# NIBB.net
KiCad netlist of a schematic drawn in EAGLE
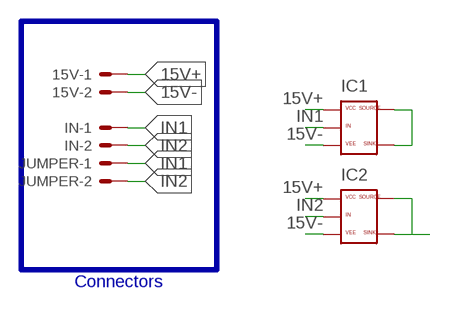
[diagram p0: schematic, sheet 1]

(export (version "E")
  (design (tool "Eeschema 10.0.6"))
  (components
    (comp (ref "15V")
      (value "22-23-2021")
      (footprint "eagle-import:22-23-2021")
      (fields (field (name "MF") "MOLEX"))
      (libsource (lib "eagle-import") (part "22-23-2021"))
    )
    (comp (ref "IC1")
      (value "ZXGD3006E6")
      (footprint "eagle-import:SOT23")
      (libsource (lib "eagle-import") (part "ZXGD3006E6"))
    )
    (comp (ref "IC2")
      (value "ZXGD3006E6")
      (footprint "eagle-import:SOT23")
      (libsource (lib "eagle-import") (part "ZXGD3006E6"))
    )
    (comp (ref "IN")
      (value "22-23-2021")
      (footprint "eagle-import:22-23-2021")
      (fields (field (name "MF") "MOLEX"))
      (libsource (lib "eagle-import") (part "22-23-2021"))
    )
    (comp (ref "JUMPER")
      (value "22-23-2021")
      (footprint "eagle-import:22-23-2021")
      (fields (field (name "MF") "MOLEX"))
      (libsource (lib "eagle-import") (part "22-23-2021"))
    )
  )
  (nets
    (net (code "1") (name "15V+") (class "Default")
      (node (ref "15V") (pin "1") (pinfunction "S_1") (pintype "passive"))
      (node (ref "IC1") (pin "1") (pinfunction "VCC_1") (pintype "bidirectional"))
      (node (ref "IC2") (pin "1") (pinfunction "VCC_1") (pintype "bidirectional"))
    )
    (net (code "2") (name "15V-") (class "Default")
      (node (ref "15V") (pin "2") (pinfunction "S_2") (pintype "passive"))
      (node (ref "IC1") (pin "3") (pinfunction "VEE_3") (pintype "bidirectional"))
      (node (ref "IC2") (pin "3") (pinfunction "VEE_3") (pintype "bidirectional"))
    )
    (net (code "3") (name "IN1") (class "Default")
      (node (ref "IC1") (pin "2") (pinfunction "IN_2") (pintype "bidirectional"))
      (node (ref "IN") (pin "1") (pinfunction "S_1") (pintype "passive"))
      (node (ref "JUMPER") (pin "1") (pinfunction "S_1") (pintype "passive"))
    )
    (net (code "4") (name "IN2") (class "Default")
      (node (ref "IC2") (pin "2") (pinfunction "IN_2") (pintype "bidirectional"))
      (node (ref "IN") (pin "2") (pinfunction "S_2") (pintype "passive"))
      (node (ref "JUMPER") (pin "2") (pinfunction "S_2") (pintype "passive"))
    )
    (net (code "5") (name "Net-(IC1-SINK)") (class "Default")
      (node (ref "IC1") (pin "4") (pinfunction "SINK_4") (pintype "bidirectional"))
      (node (ref "IC1") (pin "6") (pinfunction "SOURCE_6") (pintype "bidirectional"))
    )
    (net (code "6") (name "Net-(IC2-SINK)") (class "Default")
      (node (ref "IC2") (pin "4") (pinfunction "SINK_4") (pintype "bidirectional"))
      (node (ref "IC2") (pin "6") (pinfunction "SOURCE_6") (pintype "bidirectional"))
    )
  )
)
